# modulesShield_v1_1.net
KiCad netlist of a schematic drawn in EAGLE
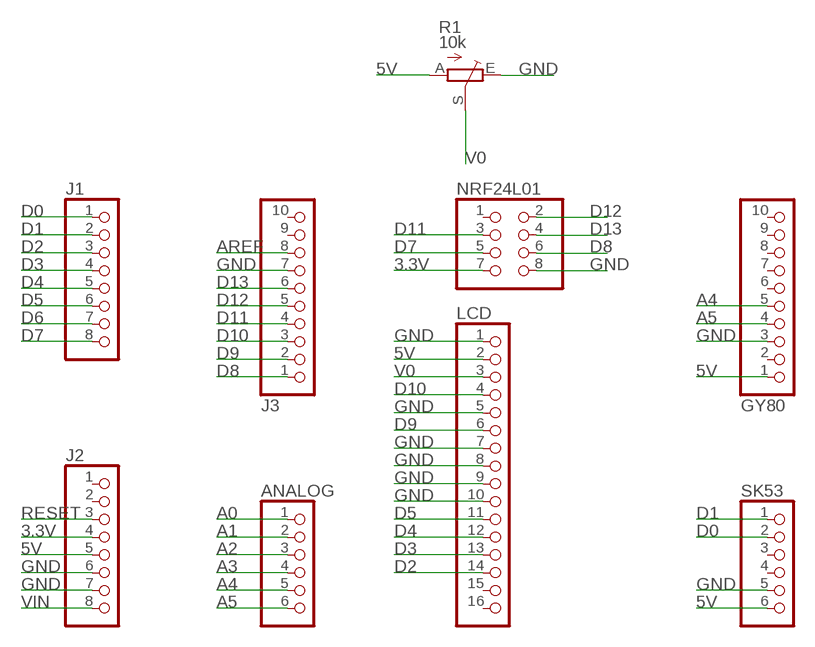
[diagram p0: schematic, sheet 1]

(export (version "E")
  (design (tool "Eeschema 10.0.6"))
  (components
    (comp (ref "ANALOG")
      (value "PINHD-1X6")
      (footprint "eagle-import:1X06")
      (libsource (lib "eagle-import") (part "PINHD-1X6"))
    )
    (comp (ref "GY80")
      (value "PINHD-1X10TH")
      (footprint "eagle-import:1X10-TH")
      (libsource (lib "eagle-import") (part "PINHD-1X10TH"))
    )
    (comp (ref "J1")
      (value "PINHD-1X8TH")
      (footprint "eagle-import:1X08-TH")
      (libsource (lib "eagle-import") (part "PINHD-1X8TH"))
    )
    (comp (ref "J2")
      (value "PINHD-1X8TH")
      (footprint "eagle-import:1X08-TH")
      (libsource (lib "eagle-import") (part "PINHD-1X8TH"))
    )
    (comp (ref "J3")
      (value "PINHD-1X10TH")
      (footprint "eagle-import:1X10-TH")
      (libsource (lib "eagle-import") (part "PINHD-1X10TH"))
    )
    (comp (ref "LCD")
      (value "PINHD-1X16")
      (footprint "eagle-import:1X16")
      (libsource (lib "eagle-import") (part "PINHD-1X16"))
    )
    (comp (ref "NRF24L01")
      (value "PINHD-2X4")
      (footprint "eagle-import:2X04")
      (libsource (lib "eagle-import") (part "PINHD-2X4"))
    )
    (comp (ref "R1")
      (value "10k")
      (footprint "eagle-import:CA6V")
      (libsource (lib "eagle-import") (part "TRIM_EU-CA6V"))
    )
    (comp (ref "SK53")
      (value "PINHD-1X6")
      (footprint "eagle-import:1X06")
      (libsource (lib "eagle-import") (part "PINHD-1X6"))
    )
  )
  (nets
    (net (code "1") (name "/3.3V") (class "Default")
      (node (ref "J2") (pin "4") (pinfunction "4_4") (pintype "passive"))
      (node (ref "NRF24L01") (pin "7") (pinfunction "7_7") (pintype "passive"))
    )
    (net (code "2") (name "/5V") (class "Default")
      (node (ref "GY80") (pin "1") (pinfunction "1_1") (pintype "passive"))
      (node (ref "J2") (pin "5") (pinfunction "5_5") (pintype "passive"))
      (node (ref "LCD") (pin "2") (pinfunction "2_2") (pintype "passive"))
      (node (ref "R1") (pin "A") (pinfunction "A_A") (pintype "passive"))
      (node (ref "SK53") (pin "6") (pinfunction "6_6") (pintype "passive"))
    )
    (net (code "3") (name "/A0") (class "Default")
      (node (ref "ANALOG") (pin "1") (pinfunction "1_1") (pintype "passive"))
    )
    (net (code "4") (name "/A1") (class "Default")
      (node (ref "ANALOG") (pin "2") (pinfunction "2_2") (pintype "passive"))
    )
    (net (code "5") (name "/A2") (class "Default")
      (node (ref "ANALOG") (pin "3") (pinfunction "3_3") (pintype "passive"))
    )
    (net (code "6") (name "/A3") (class "Default")
      (node (ref "ANALOG") (pin "4") (pinfunction "4_4") (pintype "passive"))
    )
    (net (code "7") (name "/A4") (class "Default")
      (node (ref "ANALOG") (pin "5") (pinfunction "5_5") (pintype "passive"))
      (node (ref "GY80") (pin "5") (pinfunction "5_5") (pintype "passive"))
    )
    (net (code "8") (name "/A5") (class "Default")
      (node (ref "ANALOG") (pin "6") (pinfunction "6_6") (pintype "passive"))
      (node (ref "GY80") (pin "4") (pinfunction "4_4") (pintype "passive"))
    )
    (net (code "9") (name "/AREF") (class "Default")
      (node (ref "J3") (pin "8") (pinfunction "8_8") (pintype "passive"))
    )
    (net (code "10") (name "/D0") (class "Default")
      (node (ref "J1") (pin "1") (pinfunction "1_1") (pintype "passive"))
      (node (ref "SK53") (pin "2") (pinfunction "2_2") (pintype "passive"))
    )
    (net (code "11") (name "/D1") (class "Default")
      (node (ref "J1") (pin "2") (pinfunction "2_2") (pintype "passive"))
      (node (ref "SK53") (pin "1") (pinfunction "1_1") (pintype "passive"))
    )
    (net (code "12") (name "/D2") (class "Default")
      (node (ref "J1") (pin "3") (pinfunction "3_3") (pintype "passive"))
      (node (ref "LCD") (pin "14") (pinfunction "14_14") (pintype "passive"))
    )
    (net (code "13") (name "/D3") (class "Default")
      (node (ref "J1") (pin "4") (pinfunction "4_4") (pintype "passive"))
      (node (ref "LCD") (pin "13") (pinfunction "13_13") (pintype "passive"))
    )
    (net (code "14") (name "/D4") (class "Default")
      (node (ref "J1") (pin "5") (pinfunction "5_5") (pintype "passive"))
      (node (ref "LCD") (pin "12") (pinfunction "12_12") (pintype "passive"))
    )
    (net (code "15") (name "/D5") (class "Default")
      (node (ref "J1") (pin "6") (pinfunction "6_6") (pintype "passive"))
      (node (ref "LCD") (pin "11") (pinfunction "11_11") (pintype "passive"))
    )
    (net (code "16") (name "/D6") (class "Default")
      (node (ref "J1") (pin "7") (pinfunction "7_7") (pintype "passive"))
    )
    (net (code "17") (name "/D7") (class "Default")
      (node (ref "J1") (pin "8") (pinfunction "8_8") (pintype "passive"))
      (node (ref "NRF24L01") (pin "5") (pinfunction "5_5") (pintype "passive"))
    )
    (net (code "18") (name "/D8") (class "Default")
      (node (ref "J3") (pin "1") (pinfunction "1_1") (pintype "passive"))
      (node (ref "NRF24L01") (pin "6") (pinfunction "6_6") (pintype "passive"))
    )
    (net (code "19") (name "/D9") (class "Default")
      (node (ref "J3") (pin "2") (pinfunction "2_2") (pintype "passive"))
      (node (ref "LCD") (pin "6") (pinfunction "6_6") (pintype "passive"))
    )
    (net (code "20") (name "/D10") (class "Default")
      (node (ref "J3") (pin "3") (pinfunction "3_3") (pintype "passive"))
      (node (ref "LCD") (pin "4") (pinfunction "4_4") (pintype "passive"))
    )
    (net (code "21") (name "/D11") (class "Default")
      (node (ref "J3") (pin "4") (pinfunction "4_4") (pintype "passive"))
      (node (ref "NRF24L01") (pin "3") (pinfunction "3_3") (pintype "passive"))
    )
    (net (code "22") (name "/D12") (class "Default")
      (node (ref "J3") (pin "5") (pinfunction "5_5") (pintype "passive"))
      (node (ref "NRF24L01") (pin "2") (pinfunction "2_2") (pintype "passive"))
    )
    (net (code "23") (name "/D13") (class "Default")
      (node (ref "J3") (pin "6") (pinfunction "6_6") (pintype "passive"))
      (node (ref "NRF24L01") (pin "4") (pinfunction "4_4") (pintype "passive"))
    )
    (net (code "24") (name "/GND") (class "Default")
      (node (ref "GY80") (pin "3") (pinfunction "3_3") (pintype "passive"))
      (node (ref "J2") (pin "6") (pinfunction "6_6") (pintype "passive"))
      (node (ref "J2") (pin "7") (pinfunction "7_7") (pintype "passive"))
      (node (ref "J3") (pin "7") (pinfunction "7_7") (pintype "passive"))
      (node (ref "LCD") (pin "1") (pinfunction "1_1") (pintype "passive"))
      (node (ref "LCD") (pin "10") (pinfunction "10_10") (pintype "passive"))
      (node (ref "LCD") (pin "5") (pinfunction "5_5") (pintype "passive"))
      (node (ref "LCD") (pin "7") (pinfunction "7_7") (pintype "passive"))
      (node (ref "LCD") (pin "8") (pinfunction "8_8") (pintype "passive"))
      (node (ref "LCD") (pin "9") (pinfunction "9_9") (pintype "passive"))
      (node (ref "NRF24L01") (pin "8") (pinfunction "8_8") (pintype "passive"))
      (node (ref "R1") (pin "E") (pinfunction "E_E") (pintype "passive"))
      (node (ref "SK53") (pin "5") (pinfunction "5_5") (pintype "passive"))
    )
    (net (code "25") (name "/RESET") (class "Default")
      (node (ref "J2") (pin "3") (pinfunction "3_3") (pintype "passive"))
    )
    (net (code "26") (name "/V0") (class "Default")
      (node (ref "LCD") (pin "3") (pinfunction "3_3") (pintype "passive"))
      (node (ref "R1") (pin "S") (pinfunction "S_S") (pintype "passive"))
    )
    (net (code "27") (name "/VIN") (class "Default")
      (node (ref "J2") (pin "8") (pinfunction "8_8") (pintype "passive"))
    )
    (net (code "28") (name "unconnected-(GY80-Pad2)") (class "Default")
      (node (ref "GY80") (pin "2") (pinfunction "2_2") (pintype "passive"))
    )
    (net (code "29") (name "unconnected-(GY80-Pad6)") (class "Default")
      (node (ref "GY80") (pin "6") (pinfunction "6_6") (pintype "passive"))
    )
    (net (code "30") (name "unconnected-(GY80-Pad7)") (class "Default")
      (node (ref "GY80") (pin "7") (pinfunction "7_7") (pintype "passive"))
    )
    (net (code "31") (name "unconnected-(GY80-Pad8)") (class "Default")
      (node (ref "GY80") (pin "8") (pinfunction "8_8") (pintype "passive"))
    )
    (net (code "32") (name "unconnected-(GY80-Pad9)") (class "Default")
      (node (ref "GY80") (pin "9") (pinfunction "9_9") (pintype "passive"))
    )
    (net (code "33") (name "unconnected-(GY80-Pad10)") (class "Default")
      (node (ref "GY80") (pin "10") (pinfunction "10_10") (pintype "passive"))
    )
    (net (code "34") (name "unconnected-(J2-Pad1)") (class "Default")
      (node (ref "J2") (pin "1") (pinfunction "1_1") (pintype "passive"))
    )
    (net (code "35") (name "unconnected-(J2-Pad2)") (class "Default")
      (node (ref "J2") (pin "2") (pinfunction "2_2") (pintype "passive"))
    )
    (net (code "36") (name "unconnected-(J3-Pad9)") (class "Default")
      (node (ref "J3") (pin "9") (pinfunction "9_9") (pintype "passive"))
    )
    (net (code "37") (name "unconnected-(J3-Pad10)") (class "Default")
      (node (ref "J3") (pin "10") (pinfunction "10_10") (pintype "passive"))
    )
    (net (code "38") (name "unconnected-(LCD-Pad15)") (class "Default")
      (node (ref "LCD") (pin "15") (pinfunction "15_15") (pintype "passive"))
    )
    (net (code "39") (name "unconnected-(LCD-Pad16)") (class "Default")
      (node (ref "LCD") (pin "16") (pinfunction "16_16") (pintype "passive"))
    )
    (net (code "40") (name "unconnected-(NRF24L01-Pad1)") (class "Default")
      (node (ref "NRF24L01") (pin "1") (pinfunction "1_1") (pintype "passive"))
    )
    (net (code "41") (name "unconnected-(SK53-Pad3)") (class "Default")
      (node (ref "SK53") (pin "3") (pinfunction "3_3") (pintype "passive"))
    )
    (net (code "42") (name "unconnected-(SK53-Pad4)") (class "Default")
      (node (ref "SK53") (pin "4") (pinfunction "4_4") (pintype "passive"))
    )
  )
)
